# PLL1.net
KiCad netlist of a schematic drawn in Altium Designer
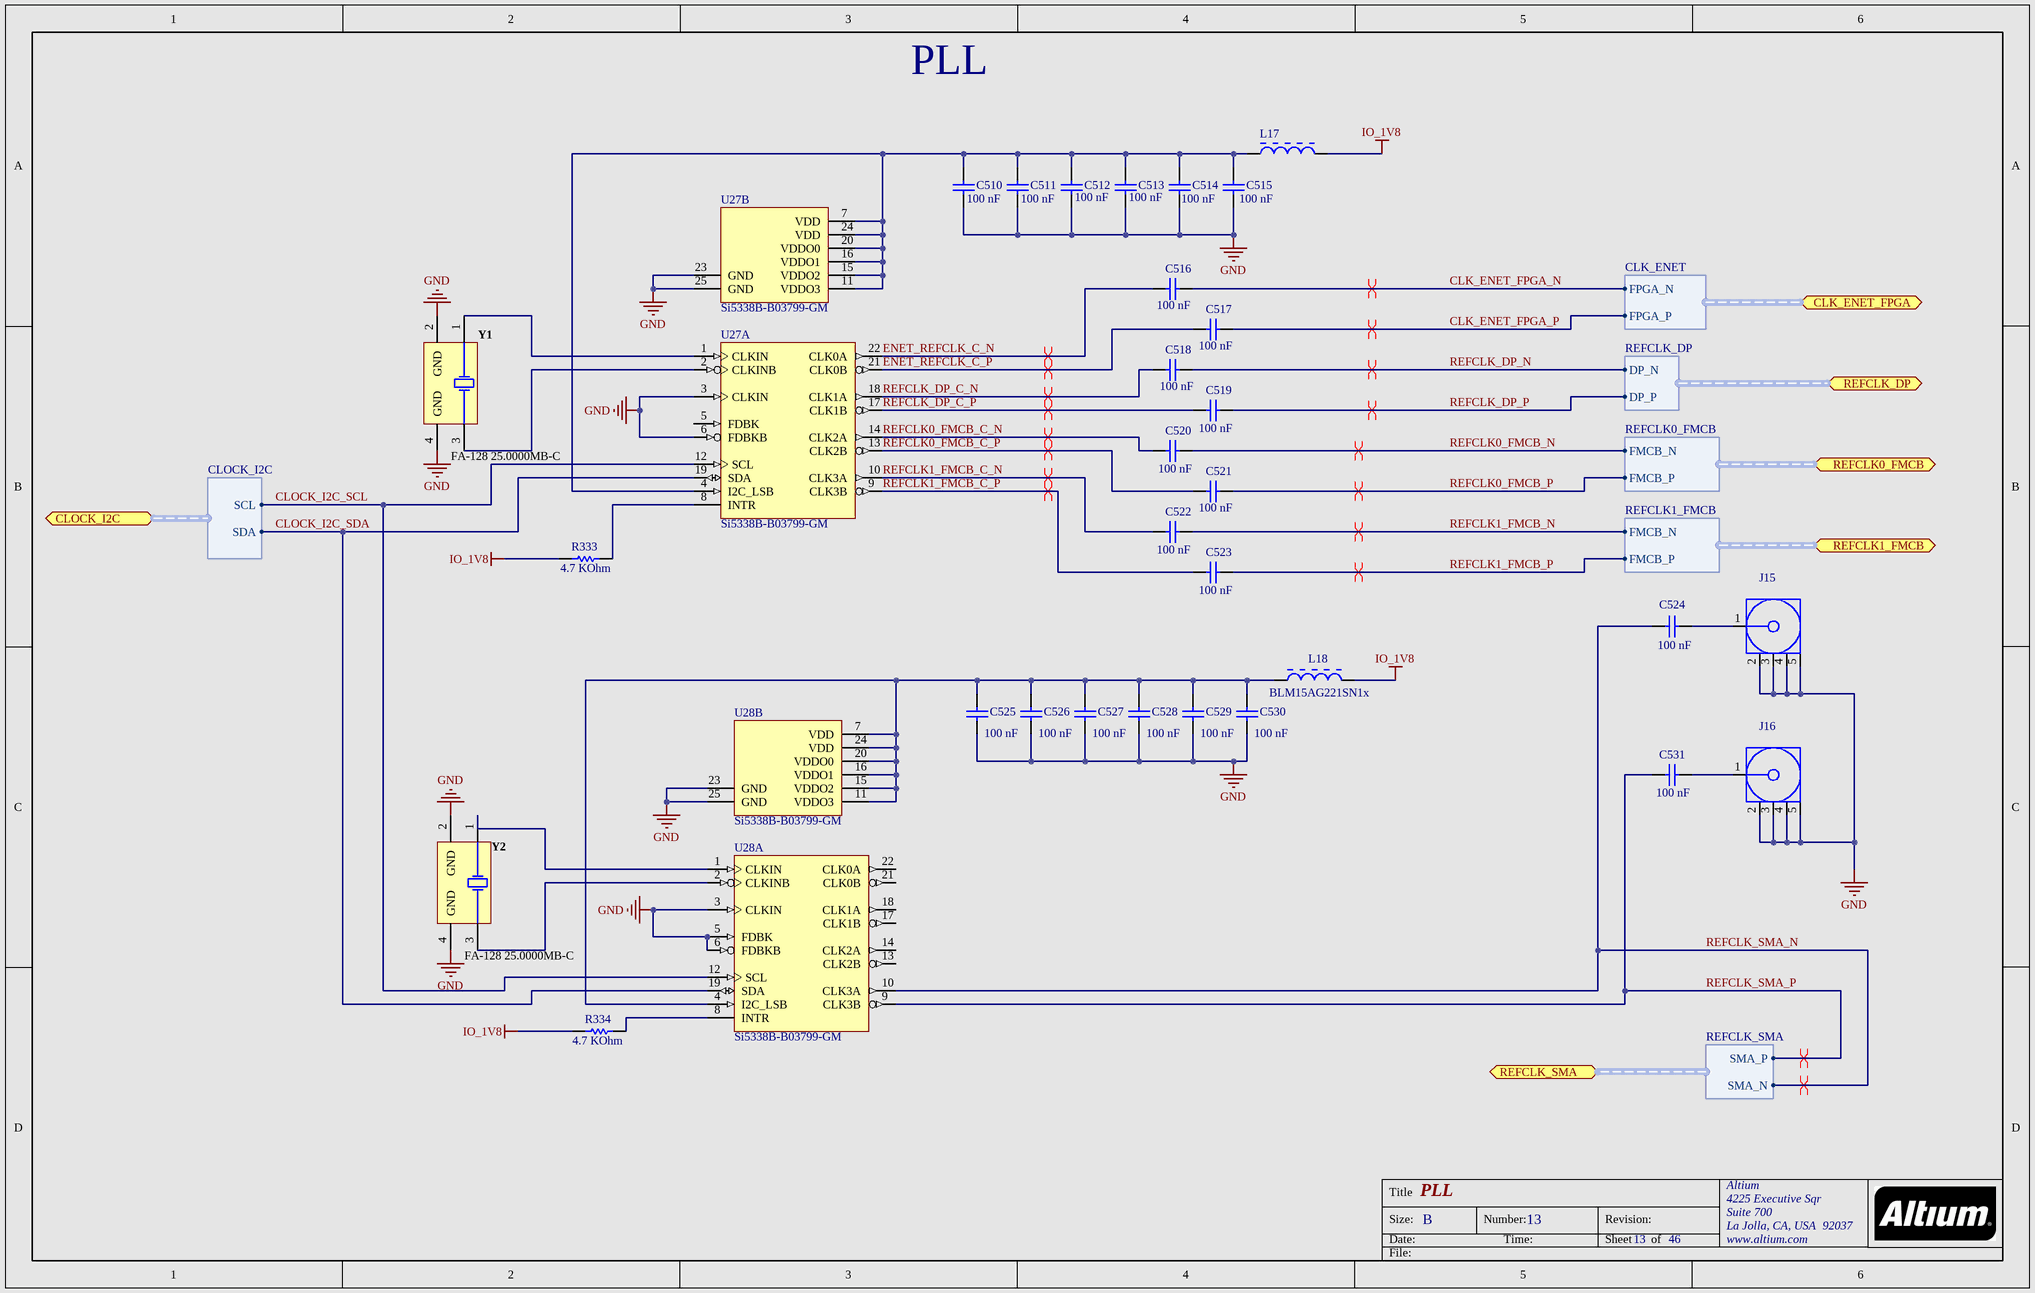
[diagram p0: PLL1.SchDoc]

(export (version "E")
  (design (tool "Eeschema 10.0.6"))
  (components
    (comp (ref "C510")
      (value "C1005X7R1E104M")
      (footprint "CAPC1005X55X10LL05")
      (description "Chip Capacitor, 0.1 uF, +/- 20%, 25 V, -55 to 125 degC, 0402 (1005 Metric), RoHS, Tape and Reel")
      (fields (field (name "TOLERANCE") "20%") (field (name "CAPACITANCE") "100 nF"))
      (libsource (lib "Altium Content Vault") (part "CAP-NP-2"))
    )
    (comp (ref "C511")
      (value "C1005X7R1E104M")
      (footprint "CAPC1005X55X10LL05")
      (description "Chip Capacitor, 0.1 uF, +/- 20%, 25 V, -55 to 125 degC, 0402 (1005 Metric), RoHS, Tape and Reel")
      (fields (field (name "TOLERANCE") "20%") (field (name "CAPACITANCE") "100 nF"))
      (libsource (lib "Altium Content Vault") (part "CAP-NP-2"))
    )
    (comp (ref "C512")
      (value "C1005X7R1E104M")
      (footprint "CAPC1005X55X10LL05")
      (description "Chip Capacitor, 0.1 uF, +/- 20%, 25 V, -55 to 125 degC, 0402 (1005 Metric), RoHS, Tape and Reel")
      (fields (field (name "TOLERANCE") "20%") (field (name "CAPACITANCE") "100 nF"))
      (libsource (lib "Altium Content Vault") (part "CAP-NP-2"))
    )
    (comp (ref "C513")
      (value "C1005X7R1E104M")
      (footprint "CAPC1005X55X10LL05")
      (description "Chip Capacitor, 0.1 uF, +/- 20%, 25 V, -55 to 125 degC, 0402 (1005 Metric), RoHS, Tape and Reel")
      (fields (field (name "TOLERANCE") "20%") (field (name "CAPACITANCE") "100 nF"))
      (libsource (lib "Altium Content Vault") (part "CAP-NP-2"))
    )
    (comp (ref "C514")
      (value "C1005X7R1E104M")
      (footprint "CAPC1005X55X10LL05")
      (description "Chip Capacitor, 0.1 uF, +/- 20%, 25 V, -55 to 125 degC, 0402 (1005 Metric), RoHS, Tape and Reel")
      (fields (field (name "TOLERANCE") "20%") (field (name "CAPACITANCE") "100 nF"))
      (libsource (lib "Altium Content Vault") (part "CAP-NP-2"))
    )
    (comp (ref "C515")
      (value "C1005X7R1E104M")
      (footprint "CAPC1005X55X10LL05")
      (description "Chip Capacitor, 0.1 uF, +/- 20%, 25 V, -55 to 125 degC, 0402 (1005 Metric), RoHS, Tape and Reel")
      (fields (field (name "TOLERANCE") "20%") (field (name "CAPACITANCE") "100 nF"))
      (libsource (lib "Altium Content Vault") (part "CAP-NP-2"))
    )
    (comp (ref "C516")
      (value "C1005X7R1E104M")
      (footprint "CAPC1005X55X10LL05")
      (description "Chip Capacitor, 0.1 uF, +/- 20%, 25 V, -55 to 125 degC, 0402 (1005 Metric), RoHS, Tape and Reel")
      (fields (field (name "TOLERANCE") "20%") (field (name "CAPACITANCE") "100 nF"))
      (libsource (lib "Altium Content Vault") (part "CAP-NP-2"))
    )
    (comp (ref "C517")
      (value "C1005X7R1E104M")
      (footprint "CAPC1005X55X10LL05")
      (description "Chip Capacitor, 0.1 uF, +/- 20%, 25 V, -55 to 125 degC, 0402 (1005 Metric), RoHS, Tape and Reel")
      (fields (field (name "TOLERANCE") "20%") (field (name "CAPACITANCE") "100 nF"))
      (libsource (lib "Altium Content Vault") (part "CAP-NP-2"))
    )
    (comp (ref "C518")
      (value "C1005X7R1E104M")
      (footprint "CAPC1005X55X10LL05")
      (description "Chip Capacitor, 0.1 uF, +/- 20%, 25 V, -55 to 125 degC, 0402 (1005 Metric), RoHS, Tape and Reel")
      (fields (field (name "TOLERANCE") "20%") (field (name "CAPACITANCE") "100 nF"))
      (libsource (lib "Altium Content Vault") (part "CAP-NP-2"))
    )
    (comp (ref "C519")
      (value "C1005X7R1E104M")
      (footprint "CAPC1005X55X10LL05")
      (description "Chip Capacitor, 0.1 uF, +/- 20%, 25 V, -55 to 125 degC, 0402 (1005 Metric), RoHS, Tape and Reel")
      (fields (field (name "TOLERANCE") "20%") (field (name "CAPACITANCE") "100 nF"))
      (libsource (lib "Altium Content Vault") (part "CAP-NP-2"))
    )
    (comp (ref "C520")
      (value "C1005X7R1E104M")
      (footprint "CAPC1005X55X10LL05")
      (description "Chip Capacitor, 0.1 uF, +/- 20%, 25 V, -55 to 125 degC, 0402 (1005 Metric), RoHS, Tape and Reel")
      (fields (field (name "TOLERANCE") "20%") (field (name "CAPACITANCE") "100 nF"))
      (libsource (lib "Altium Content Vault") (part "CAP-NP-2"))
    )
    (comp (ref "C521")
      (value "C1005X7R1E104M")
      (footprint "CAPC1005X55X10LL05")
      (description "Chip Capacitor, 0.1 uF, +/- 20%, 25 V, -55 to 125 degC, 0402 (1005 Metric), RoHS, Tape and Reel")
      (fields (field (name "TOLERANCE") "20%") (field (name "CAPACITANCE") "100 nF"))
      (libsource (lib "Altium Content Vault") (part "CAP-NP-2"))
    )
    (comp (ref "C522")
      (value "C1005X7R1E104M")
      (footprint "CAPC1005X55X10LL05")
      (description "Chip Capacitor, 0.1 uF, +/- 20%, 25 V, -55 to 125 degC, 0402 (1005 Metric), RoHS, Tape and Reel")
      (fields (field (name "TOLERANCE") "20%") (field (name "CAPACITANCE") "100 nF"))
      (libsource (lib "Altium Content Vault") (part "CAP-NP-2"))
    )
    (comp (ref "C523")
      (value "C1005X7R1E104M")
      (footprint "CAPC1005X55X10LL05")
      (description "Chip Capacitor, 0.1 uF, +/- 20%, 25 V, -55 to 125 degC, 0402 (1005 Metric), RoHS, Tape and Reel")
      (fields (field (name "TOLERANCE") "20%") (field (name "CAPACITANCE") "100 nF"))
      (libsource (lib "Altium Content Vault") (part "CAP-NP-2"))
    )
    (comp (ref "C524")
      (value "C1005X7R1E104M")
      (footprint "CAPC1005X55X10LL05")
      (description "Chip Capacitor, 0.1 uF, +/- 20%, 25 V, -55 to 125 degC, 0402 (1005 Metric), RoHS, Tape and Reel")
      (fields (field (name "TOLERANCE") "20%") (field (name "CAPACITANCE") "100 nF"))
      (libsource (lib "Altium Content Vault") (part "CAP-NP-2"))
    )
    (comp (ref "C525")
      (value "C1005X7R1E104M")
      (footprint "CAPC1005X55X10LL05")
      (description "Chip Capacitor, 0.1 uF, +/- 20%, 25 V, -55 to 125 degC, 0402 (1005 Metric), RoHS, Tape and Reel")
      (fields (field (name "TOLERANCE") "20%") (field (name "CAPACITANCE") "100 nF"))
      (libsource (lib "Altium Content Vault") (part "CAP-NP-2"))
    )
    (comp (ref "C526")
      (value "C1005X7R1E104M")
      (footprint "CAPC1005X55X10LL05")
      (description "Chip Capacitor, 0.1 uF, +/- 20%, 25 V, -55 to 125 degC, 0402 (1005 Metric), RoHS, Tape and Reel")
      (fields (field (name "TOLERANCE") "20%") (field (name "CAPACITANCE") "100 nF"))
      (libsource (lib "Altium Content Vault") (part "CAP-NP-2"))
    )
    (comp (ref "C527")
      (value "C1005X7R1E104M")
      (footprint "CAPC1005X55X10LL05")
      (description "Chip Capacitor, 0.1 uF, +/- 20%, 25 V, -55 to 125 degC, 0402 (1005 Metric), RoHS, Tape and Reel")
      (fields (field (name "TOLERANCE") "20%") (field (name "CAPACITANCE") "100 nF"))
      (libsource (lib "Altium Content Vault") (part "CAP-NP-2"))
    )
    (comp (ref "C528")
      (value "C1005X7R1E104M")
      (footprint "CAPC1005X55X10LL05")
      (description "Chip Capacitor, 0.1 uF, +/- 20%, 25 V, -55 to 125 degC, 0402 (1005 Metric), RoHS, Tape and Reel")
      (fields (field (name "TOLERANCE") "20%") (field (name "CAPACITANCE") "100 nF"))
      (libsource (lib "Altium Content Vault") (part "CAP-NP-2"))
    )
    (comp (ref "C529")
      (value "C1005X7R1E104M")
      (footprint "CAPC1005X55X10LL05")
      (description "Chip Capacitor, 0.1 uF, +/- 20%, 25 V, -55 to 125 degC, 0402 (1005 Metric), RoHS, Tape and Reel")
      (fields (field (name "TOLERANCE") "20%") (field (name "CAPACITANCE") "100 nF"))
      (libsource (lib "Altium Content Vault") (part "CAP-NP-2"))
    )
    (comp (ref "C530")
      (value "C1005X7R1E104M")
      (footprint "CAPC1005X55X10LL05")
      (description "Chip Capacitor, 0.1 uF, +/- 20%, 25 V, -55 to 125 degC, 0402 (1005 Metric), RoHS, Tape and Reel")
      (fields (field (name "TOLERANCE") "20%") (field (name "CAPACITANCE") "100 nF"))
      (libsource (lib "Altium Content Vault") (part "CAP-NP-2"))
    )
    (comp (ref "C531")
      (value "C1005X7R1E104M")
      (footprint "CAPC1005X55X10LL05")
      (description "Chip Capacitor, 0.1 uF, +/- 20%, 25 V, -55 to 125 degC, 0402 (1005 Metric), RoHS, Tape and Reel")
      (fields (field (name "TOLERANCE") "20%") (field (name "CAPACITANCE") "100 nF"))
      (libsource (lib "Altium Content Vault") (part "CAP-NP-2"))
    )
    (comp (ref "J15")
      (value "LTI-SASF54GT")
      (footprint "LHT-LTI-SASF54GT_V")
      (description "SMA Connector, Pitch 2.54 mm, 1 Position, Height 9.5 mm, Tail Length 4 mm, RoHS")
      (fields (field (name "MANUFACTURER") "Lighthorse Technologies Inc."))
      (libsource (lib "Altium Content Vault") (part "CMP-1713-00001-1"))
    )
    (comp (ref "J16")
      (value "LTI-SASF54GT")
      (footprint "LHT-LTI-SASF54GT_V")
      (description "SMA Connector, Pitch 2.54 mm, 1 Position, Height 9.5 mm, Tail Length 4 mm, RoHS")
      (fields (field (name "MANUFACTURER") "Lighthorse Technologies Inc."))
      (libsource (lib "Altium Content Vault") (part "CMP-1713-00001-1"))
    )
    (comp (ref "L17")
      (value "BLM15AG221SN1J")
      (footprint "MURA-BLM15-CHIP-2_V")
      (fields (field (name "MANUFACTURER") "Murata"))
      (libsource (lib "Altium Content Vault") (part "CMP-0686-00186-2"))
    )
    (comp (ref "L18")
      (value "BLM15AG221SN1x")
      (footprint "MURA-BLM15AG221SN1x_V")
      (description "Chip Bead, 220 Ohm, +/- 25 %, 100 MHz, 300 mA, -55 to 125 degC, 0402 (1005 Metric), RoHS")
      (fields (field (name "TOLERANCE") "25%"))
      (libsource (lib "Altium Content Vault") (part "BEAD-2"))
    )
    (comp (ref "R333")
      (value "ERJ-2RKF4701X")
      (footprint "RESC1005X40X25LL05T05")
      (description "Chip Resistor, 4.7 KOhm, +/- 1%, 0.1 W, -55 to 155 degC, 0402 (1005 Metric), RoHS, Tape and Reel")
      (fields (field (name "TOLERANCE") "1%") (field (name "RESISTANCE") "4.7 KOhm"))
      (libsource (lib "Altium Content Vault") (part "RES-2"))
    )
    (comp (ref "R334")
      (value "ERJ-2RKF4701X")
      (footprint "RESC1005X40X25LL05T05")
      (description "Chip Resistor, 4.7 KOhm, +/- 1%, 0.1 W, -55 to 155 degC, 0402 (1005 Metric), RoHS, Tape and Reel")
      (fields (field (name "TOLERANCE") "1%") (field (name "RESISTANCE") "4.7 KOhm"))
      (libsource (lib "Altium Content Vault") (part "RES-2"))
    )
    (comp (ref "U27")
      (value "Si5338B-B03799-GM")
      (footprint "SLAB-QFN-24-2550x2550TP_V")
      (fields (field (name "MANUFACTURER") "Silicon Labs"))
      (libsource (lib "") (part "CMP-1706-00002-1_1"))
    )
    (comp (ref "U28")
      (value "Si5338B-B03799-GM")
      (footprint "SLAB-QFN-24-2550x2550TP_V")
      (fields (field (name "MANUFACTURER") "Silicon Labs"))
      (libsource (lib "") (part "CMP-1706-00002-1_1"))
    )
    (comp (ref "Y1")
      (value "FA-128 25.0000MB-C")
      (footprint "EPSON-FA-128_V")
      (description "Range Crystal Unit, 25 MHz, -40 to 85 degC, 4-Pin SMD, RoHS, Tape and Reel")
      (libsource (lib "Altium Content Vault") (part "XTAL-1-3-4"))
    )
    (comp (ref "Y2")
      (value "FA-128 25.0000MB-C")
      (footprint "EPSON-FA-128_V")
      (description "Range Crystal Unit, 25 MHz, -40 to 85 degC, 4-Pin SMD, RoHS, Tape and Reel")
      (libsource (lib "Altium Content Vault") (part "XTAL-1-3-4"))
    )
  )
  (nets
    (net (code "7") (name "/CLK_ENET_FPGA_N") (class "Default")
      (node (ref "C516") (pin "2") (pinfunction "2_2") (pintype "passive"))
    )
    (net (code "8") (name "/CLK_ENET_FPGA_P") (class "Default")
      (node (ref "C517") (pin "2") (pinfunction "2_2") (pintype "passive"))
    )
    (net (code "9") (name "/CLOCK_I2C_SCL") (class "Default")
      (node (ref "U27") (pin "12") (pinfunction "SCL_12") (pintype "input"))
      (node (ref "U28") (pin "12") (pinfunction "SCL_12") (pintype "input"))
    )
    (net (code "10") (name "/CLOCK_I2C_SDA") (class "Default")
      (node (ref "U27") (pin "19") (pinfunction "SDA_19") (pintype "bidirectional"))
      (node (ref "U28") (pin "19") (pinfunction "SDA_19") (pintype "bidirectional"))
    )
    (net (code "11") (name "/ENET_REFCLK_C_N") (class "Default")
      (node (ref "C516") (pin "1") (pinfunction "1_1") (pintype "passive"))
      (node (ref "U27") (pin "22") (pinfunction "CLK0A_22") (pintype "output"))
    )
    (net (code "12") (name "/ENET_REFCLK_C_P") (class "Default")
      (node (ref "C517") (pin "1") (pinfunction "1_1") (pintype "passive"))
      (node (ref "U27") (pin "21") (pinfunction "CLK0B_21") (pintype "output"))
    )
    (net (code "13") (name "/REFCLK0_FMCB_C_N") (class "Default")
      (node (ref "C520") (pin "1") (pinfunction "1_1") (pintype "passive"))
      (node (ref "U27") (pin "14") (pinfunction "CLK2A_14") (pintype "output"))
    )
    (net (code "14") (name "/REFCLK0_FMCB_C_P") (class "Default")
      (node (ref "C521") (pin "1") (pinfunction "1_1") (pintype "passive"))
      (node (ref "U27") (pin "13") (pinfunction "CLK2B_13") (pintype "output"))
    )
    (net (code "15") (name "/REFCLK0_FMCB_N") (class "Default")
      (node (ref "C520") (pin "2") (pinfunction "2_2") (pintype "passive"))
    )
    (net (code "16") (name "/REFCLK0_FMCB_P") (class "Default")
      (node (ref "C521") (pin "2") (pinfunction "2_2") (pintype "passive"))
    )
    (net (code "17") (name "/REFCLK1_FMCB_C_N") (class "Default")
      (node (ref "C522") (pin "1") (pinfunction "1_1") (pintype "passive"))
      (node (ref "U27") (pin "10") (pinfunction "CLK3A_10") (pintype "output"))
    )
    (net (code "18") (name "/REFCLK1_FMCB_C_P") (class "Default")
      (node (ref "C523") (pin "1") (pinfunction "1_1") (pintype "passive"))
      (node (ref "U27") (pin "9") (pinfunction "CLK3B_9") (pintype "output"))
    )
    (net (code "19") (name "/REFCLK1_FMCB_N") (class "Default")
      (node (ref "C522") (pin "2") (pinfunction "2_2") (pintype "passive"))
    )
    (net (code "20") (name "/REFCLK1_FMCB_P") (class "Default")
      (node (ref "C523") (pin "2") (pinfunction "2_2") (pintype "passive"))
    )
    (net (code "21") (name "/REFCLK_DP_C_N") (class "Default")
      (node (ref "C518") (pin "1") (pinfunction "1_1") (pintype "passive"))
      (node (ref "U27") (pin "18") (pinfunction "CLK1A_18") (pintype "output"))
    )
    (net (code "22") (name "/REFCLK_DP_C_P") (class "Default")
      (node (ref "C519") (pin "1") (pinfunction "1_1") (pintype "passive"))
      (node (ref "U27") (pin "17") (pinfunction "CLK1B_17") (pintype "output"))
    )
    (net (code "23") (name "/REFCLK_DP_N") (class "Default")
      (node (ref "C518") (pin "2") (pinfunction "2_2") (pintype "passive"))
    )
    (net (code "24") (name "/REFCLK_DP_P") (class "Default")
      (node (ref "C519") (pin "2") (pinfunction "2_2") (pintype "passive"))
    )
    (net (code "25") (name "/REFCLK_SMA_N") (class "Default")
      (node (ref "C524") (pin "1") (pinfunction "1_1") (pintype "passive"))
      (node (ref "U28") (pin "10") (pinfunction "CLK3A_10") (pintype "output"))
    )
    (net (code "26") (name "/REFCLK_SMA_P") (class "Default")
      (node (ref "C531") (pin "1") (pinfunction "1_1") (pintype "passive"))
      (node (ref "U28") (pin "9") (pinfunction "CLK3B_9") (pintype "output"))
    )
    (net (code "33") (name "GND") (class "Default")
      (node (ref "C510") (pin "2") (pinfunction "2_2") (pintype "passive"))
      (node (ref "C511") (pin "2") (pinfunction "2_2") (pintype "passive"))
      (node (ref "C512") (pin "2") (pinfunction "2_2") (pintype "passive"))
      (node (ref "C513") (pin "2") (pinfunction "2_2") (pintype "passive"))
      (node (ref "C514") (pin "2") (pinfunction "2_2") (pintype "passive"))
      (node (ref "C515") (pin "2") (pinfunction "2_2") (pintype "passive"))
      (node (ref "C525") (pin "2") (pinfunction "2_2") (pintype "passive"))
      (node (ref "C526") (pin "2") (pinfunction "2_2") (pintype "passive"))
      (node (ref "C527") (pin "2") (pinfunction "2_2") (pintype "passive"))
      (node (ref "C528") (pin "2") (pinfunction "2_2") (pintype "passive"))
      (node (ref "C529") (pin "2") (pinfunction "2_2") (pintype "passive"))
      (node (ref "C530") (pin "2") (pinfunction "2_2") (pintype "passive"))
      (node (ref "J15") (pin "2") (pinfunction "2_2") (pintype "passive"))
      (node (ref "J15") (pin "3") (pinfunction "3_3") (pintype "passive"))
      (node (ref "J15") (pin "4") (pinfunction "4_4") (pintype "passive"))
      (node (ref "J15") (pin "5") (pinfunction "5_5") (pintype "passive"))
      (node (ref "J16") (pin "2") (pinfunction "2_2") (pintype "passive"))
      (node (ref "J16") (pin "3") (pinfunction "3_3") (pintype "passive"))
      (node (ref "J16") (pin "4") (pinfunction "4_4") (pintype "passive"))
      (node (ref "J16") (pin "5") (pinfunction "5_5") (pintype "passive"))
      (node (ref "U27") (pin "23") (pinfunction "GND_23") (pintype "power_in"))
      (node (ref "U27") (pin "25") (pinfunction "GND_25") (pintype "power_in"))
      (node (ref "U27") (pin "3") (pinfunction "CLKIN_3") (pintype "input"))
      (node (ref "U27") (pin "6") (pinfunction "FDBKB_6") (pintype "input"))
      (node (ref "U28") (pin "23") (pinfunction "GND_23") (pintype "power_in"))
      (node (ref "U28") (pin "25") (pinfunction "GND_25") (pintype "power_in"))
      (node (ref "U28") (pin "3") (pinfunction "CLKIN_3") (pintype "input"))
      (node (ref "U28") (pin "5") (pinfunction "FDBK_5") (pintype "input"))
      (node (ref "U28") (pin "6") (pinfunction "FDBKB_6") (pintype "input"))
      (node (ref "Y1") (pin "2") (pinfunction "GND_2") (pintype "power_in"))
      (node (ref "Y1") (pin "4") (pinfunction "GND_4") (pintype "power_in"))
      (node (ref "Y2") (pin "2") (pinfunction "GND_2") (pintype "power_in"))
      (node (ref "Y2") (pin "4") (pinfunction "GND_4") (pintype "power_in"))
    )
    (net (code "34") (name "IO_1V8") (class "Default")
      (node (ref "L17") (pin "2") (pinfunction "2_2") (pintype "passive"))
      (node (ref "L18") (pin "2") (pinfunction "2_2") (pintype "passive"))
      (node (ref "R333") (pin "1") (pinfunction "1_1") (pintype "passive"))
      (node (ref "R334") (pin "1") (pinfunction "1_1") (pintype "passive"))
    )
    (net (code "35") (name "Net-(C524-Pad2)") (class "Default")
      (node (ref "C524") (pin "2") (pinfunction "2_2") (pintype "passive"))
      (node (ref "J15") (pin "1") (pinfunction "1_1") (pintype "passive"))
    )
    (net (code "36") (name "Net-(C531-Pad2)") (class "Default")
      (node (ref "C531") (pin "2") (pinfunction "2_2") (pintype "passive"))
      (node (ref "J16") (pin "1") (pinfunction "1_1") (pintype "passive"))
    )
    (net (code "37") (name "Net-(U27A-CLKINB)") (class "Default")
      (node (ref "U27") (pin "2") (pinfunction "CLKINB_2") (pintype "input"))
      (node (ref "Y1") (pin "3") (pinfunction "X2_3") (pintype "passive"))
    )
    (net (code "38") (name "Net-(U27A-I2C_LSB)") (class "Default")
      (node (ref "C510") (pin "1") (pinfunction "1_1") (pintype "passive"))
      (node (ref "C511") (pin "1") (pinfunction "1_1") (pintype "passive"))
      (node (ref "C512") (pin "1") (pinfunction "1_1") (pintype "passive"))
      (node (ref "C513") (pin "1") (pinfunction "1_1") (pintype "passive"))
      (node (ref "C514") (pin "1") (pinfunction "1_1") (pintype "passive"))
      (node (ref "C515") (pin "1") (pinfunction "1_1") (pintype "passive"))
      (node (ref "L17") (pin "1") (pinfunction "1_1") (pintype "passive"))
      (node (ref "U27") (pin "11") (pinfunction "VDDO3_11") (pintype "power_in"))
      (node (ref "U27") (pin "15") (pinfunction "VDDO2_15") (pintype "power_in"))
      (node (ref "U27") (pin "16") (pinfunction "VDDO1_16") (pintype "power_in"))
      (node (ref "U27") (pin "20") (pinfunction "VDDO0_20") (pintype "power_in"))
      (node (ref "U27") (pin "24") (pinfunction "VDD_24") (pintype "power_in"))
      (node (ref "U27") (pin "4") (pinfunction "I2C_LSB_4") (pintype "input"))
      (node (ref "U27") (pin "7") (pinfunction "VDD_7") (pintype "power_in"))
    )
    (net (code "39") (name "Net-(U27A-INTR)") (class "Default")
      (node (ref "R333") (pin "2") (pinfunction "2_2") (pintype "passive"))
      (node (ref "U27") (pin "8") (pinfunction "INTR_8") (pintype "open_collector"))
    )
    (net (code "40") (name "Net-(U28A-CLKINB)") (class "Default")
      (node (ref "U28") (pin "2") (pinfunction "CLKINB_2") (pintype "input"))
      (node (ref "Y2") (pin "3") (pinfunction "X2_3") (pintype "passive"))
    )
    (net (code "41") (name "Net-(U28A-I2C_LSB)") (class "Default")
      (node (ref "C525") (pin "1") (pinfunction "1_1") (pintype "passive"))
      (node (ref "C526") (pin "1") (pinfunction "1_1") (pintype "passive"))
      (node (ref "C527") (pin "1") (pinfunction "1_1") (pintype "passive"))
      (node (ref "C528") (pin "1") (pinfunction "1_1") (pintype "passive"))
      (node (ref "C529") (pin "1") (pinfunction "1_1") (pintype "passive"))
      (node (ref "C530") (pin "1") (pinfunction "1_1") (pintype "passive"))
      (node (ref "L18") (pin "1") (pinfunction "1_1") (pintype "passive"))
      (node (ref "U28") (pin "11") (pinfunction "VDDO3_11") (pintype "power_in"))
      (node (ref "U28") (pin "15") (pinfunction "VDDO2_15") (pintype "power_in"))
      (node (ref "U28") (pin "16") (pinfunction "VDDO1_16") (pintype "power_in"))
      (node (ref "U28") (pin "20") (pinfunction "VDDO0_20") (pintype "power_in"))
      (node (ref "U28") (pin "24") (pinfunction "VDD_24") (pintype "power_in"))
      (node (ref "U28") (pin "4") (pinfunction "I2C_LSB_4") (pintype "input"))
      (node (ref "U28") (pin "7") (pinfunction "VDD_7") (pintype "power_in"))
    )
    (net (code "42") (name "Net-(U28A-INTR)") (class "Default")
      (node (ref "R334") (pin "2") (pinfunction "2_2") (pintype "passive"))
      (node (ref "U28") (pin "8") (pinfunction "INTR_8") (pintype "open_collector"))
    )
    (net (code "43") (name "Net-(Y1-X1)") (class "Default")
      (node (ref "U27") (pin "1") (pinfunction "CLKIN_1") (pintype "input"))
      (node (ref "Y1") (pin "1") (pinfunction "X1_1") (pintype "passive"))
    )
    (net (code "44") (name "Net-(Y2-X1)") (class "Default")
      (node (ref "U28") (pin "1") (pinfunction "CLKIN_1") (pintype "input"))
      (node (ref "Y2") (pin "1") (pinfunction "X1_1") (pintype "passive"))
    )
    (net (code "45") (name "unconnected-(U27A-FDBK-Pad5)") (class "Default")
      (node (ref "U27") (pin "5") (pinfunction "FDBK_5") (pintype "input"))
    )
    (net (code "46") (name "unconnected-(U28A-CLK0A-Pad22)") (class "Default")
      (node (ref "U28") (pin "22") (pinfunction "CLK0A_22") (pintype "output"))
    )
    (net (code "47") (name "unconnected-(U28A-CLK0B-Pad21)") (class "Default")
      (node (ref "U28") (pin "21") (pinfunction "CLK0B_21") (pintype "output"))
    )
    (net (code "48") (name "unconnected-(U28A-CLK1A-Pad18)") (class "Default")
      (node (ref "U28") (pin "18") (pinfunction "CLK1A_18") (pintype "output"))
    )
    (net (code "49") (name "unconnected-(U28A-CLK1B-Pad17)") (class "Default")
      (node (ref "U28") (pin "17") (pinfunction "CLK1B_17") (pintype "output"))
    )
    (net (code "50") (name "unconnected-(U28A-CLK2A-Pad14)") (class "Default")
      (node (ref "U28") (pin "14") (pinfunction "CLK2A_14") (pintype "output"))
    )
    (net (code "51") (name "unconnected-(U28A-CLK2B-Pad13)") (class "Default")
      (node (ref "U28") (pin "13") (pinfunction "CLK2B_13") (pintype "output"))
    )
  )
)
